# sb-sonata-industriaal.net
KiCad netlist of a schematic drawn in Altium Designer
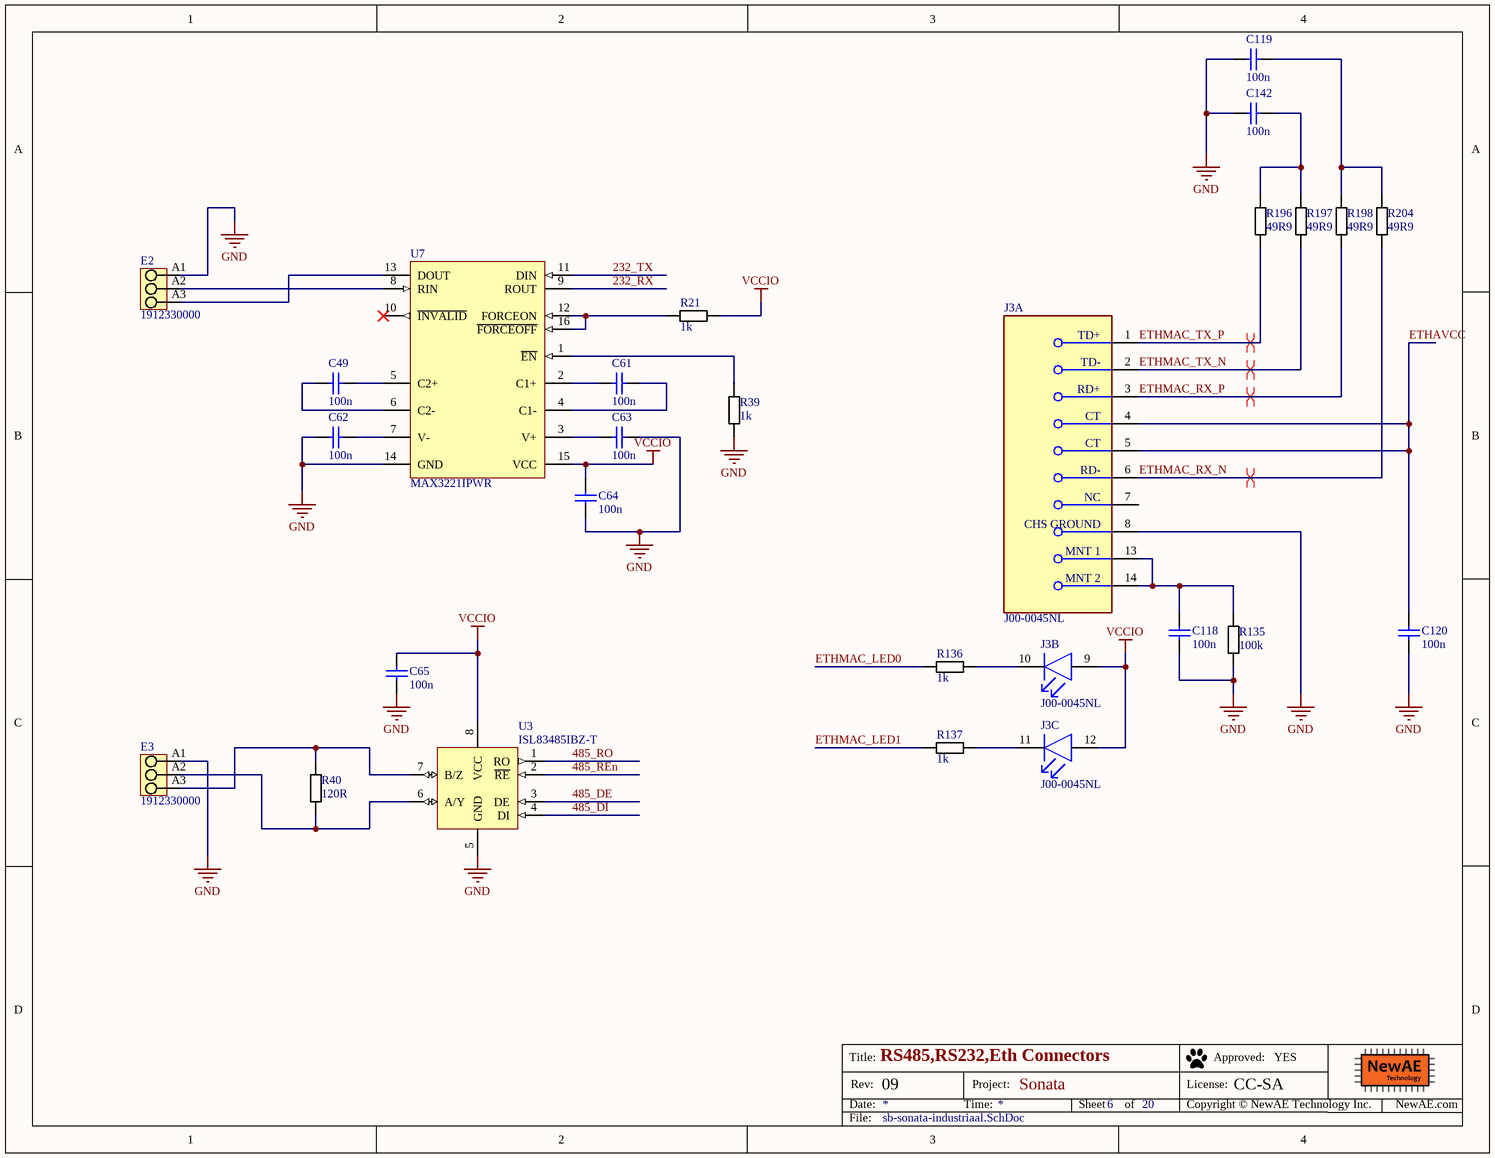
[diagram p0: sb-sonata-industriaal.SchDoc]

(export (version "E")
  (design (tool "Eeschema 10.0.6"))
  (components
    (comp (ref "C49")
      (value "100n")
      (footprint "CAPC0402_M")
      (description "100n, 0402")
      (fields (field (name "PART NUMBER") "CCHIP-100n-0402"))
      (libsource (lib "NewAE_AltiumLib") (part "CAP"))
    )
    (comp (ref "C61")
      (value "100n")
      (footprint "CAPC0402_M")
      (description "100n, 0402")
      (fields (field (name "PART NUMBER") "CCHIP-100n-0402"))
      (libsource (lib "NewAE_AltiumLib") (part "CAP"))
    )
    (comp (ref "C62")
      (value "100n")
      (footprint "CAPC0402_M")
      (description "100n, 0402")
      (fields (field (name "PART NUMBER") "CCHIP-100n-0402"))
      (libsource (lib "NewAE_AltiumLib") (part "CAP"))
    )
    (comp (ref "C63")
      (value "100n")
      (footprint "CAPC0402_M")
      (description "100n, 0402")
      (fields (field (name "PART NUMBER") "CCHIP-100n-0402"))
      (libsource (lib "NewAE_AltiumLib") (part "CAP"))
    )
    (comp (ref "C64")
      (value "100n")
      (footprint "CAPC0402_M")
      (description "100n, 0402")
      (fields (field (name "PART NUMBER") "CCHIP-100n-0402"))
      (libsource (lib "NewAE_AltiumLib") (part "CAP"))
    )
    (comp (ref "C65")
      (value "100n")
      (footprint "CAPC0402_M")
      (description "100n, 0402")
      (fields (field (name "PART NUMBER") "CCHIP-100n-0402"))
      (libsource (lib "NewAE_AltiumLib") (part "CAP"))
    )
    (comp (ref "C118")
      (value "100n")
      (footprint "CAPC0402_M")
      (description "100n, 0402")
      (fields (field (name "PART NUMBER") "CCHIP-100n-0402"))
      (libsource (lib "NewAE_AltiumLib") (part "CAP"))
    )
    (comp (ref "C119")
      (value "100n")
      (footprint "CAPC0402_M")
      (description "100n, 0402")
      (fields (field (name "PART NUMBER") "CCHIP-100n-0402"))
      (libsource (lib "NewAE_AltiumLib") (part "CAP"))
    )
    (comp (ref "C120")
      (value "100n")
      (footprint "CAPC0402_M")
      (description "100n, 0402")
      (fields (field (name "PART NUMBER") "CCHIP-100n-0402"))
      (libsource (lib "NewAE_AltiumLib") (part "CAP"))
    )
    (comp (ref "C142")
      (value "100n")
      (footprint "CAPC0402_M")
      (description "100n, 0402")
      (fields (field (name "PART NUMBER") "CCHIP-100n-0402"))
      (libsource (lib "NewAE_AltiumLib") (part "CAP"))
    )
    (comp (ref "E2")
      (value "1912330000")
      (footprint "PS_3_5_90_03")
      (description "OMNIMATE Signal - series PS")
      (fields (field (name "MANUFACTURER") "Weidmueller"))
      (libsource (lib "Altium Content Vault") (part "Terminal_03_1x03"))
    )
    (comp (ref "E3")
      (value "1912330000")
      (footprint "PS_3_5_90_03")
      (description "OMNIMATE Signal - series PS")
      (fields (field (name "MANUFACTURER") "Weidmueller"))
      (libsource (lib "Altium Content Vault") (part "Terminal_03_1x03"))
    )
    (comp (ref "J3")
      (value "J00-0045NL")
      (footprint "FP-J00-0045NL-MFG")
      (description "CONN JACK 1PORT 100 BASE-TX PCB")
      (libsource (lib "") (part "9e414223d7443300137682b695b44b7_1"))
    )
    (comp (ref "R21")
      (value "1k")
      (footprint "RESC1608X55N")
      (description "1k res, 0603, 1%, 1/10W")
      (fields (field (name "PART NUMBER") "RCHIP-1K-0603") (field (name "TOLERANCE") "1%"))
      (libsource (lib "") (part "RES-EU_1"))
    )
    (comp (ref "R39")
      (value "1k")
      (footprint "RESC1608X55N")
      (description "1k res, 0603, 1%, 1/10W")
      (fields (field (name "PART NUMBER") "RCHIP-1K-0603") (field (name "TOLERANCE") "1%"))
      (libsource (lib "") (part "RES-EU_2"))
    )
    (comp (ref "R40")
      (value "120R")
      (footprint "RESC1608X55N")
      (description "120R res, 0603, 1%, 1/10W")
      (fields (field (name "PART NUMBER") "RCHIP-120R-0603") (field (name "TOLERANCE") "1%"))
      (libsource (lib "NewAE_AltiumLib") (part "RES-EU"))
    )
    (comp (ref "R135")
      (value "100k")
      (footprint "RESC1005X40N")
      (description "100k res, 0402, 1%, 1/16W")
      (fields (field (name "PART NUMBER") "RCHIP-100K-0402") (field (name "TOLERANCE") "1%"))
      (libsource (lib "NewAE_AltiumLib") (part "RES-EU"))
    )
    (comp (ref "R136")
      (value "1k")
      (footprint "RESC1608X55N")
      (description "1k res, 0603, 1%, 1/10W")
      (fields (field (name "PART NUMBER") "RCHIP-1K-0603") (field (name "TOLERANCE") "1%"))
      (libsource (lib "") (part "RES-EU_1"))
    )
    (comp (ref "R137")
      (value "1k")
      (footprint "RESC1608X55N")
      (description "1k res, 0603, 1%, 1/10W")
      (fields (field (name "PART NUMBER") "RCHIP-1K-0603") (field (name "TOLERANCE") "1%"))
      (libsource (lib "") (part "RES-EU_1"))
    )
    (comp (ref "R196")
      (value "49R9")
      (footprint "RESC2012X70N")
      (description "49r9 res, 0805, 1%, 1/8W")
      (fields (field (name "PART NUMBER") "RCHIP-49R9-0805") (field (name "TOLERANCE") "1%"))
      (libsource (lib "NewAE_AltiumLib") (part "RES-EU"))
    )
    (comp (ref "R197")
      (value "49R9")
      (footprint "RESC2012X70N")
      (description "49r9 res, 0805, 1%, 1/8W")
      (fields (field (name "PART NUMBER") "RCHIP-49R9-0805") (field (name "TOLERANCE") "1%"))
      (libsource (lib "NewAE_AltiumLib") (part "RES-EU"))
    )
    (comp (ref "R198")
      (value "49R9")
      (footprint "RESC2012X70N")
      (description "49r9 res, 0805, 1%, 1/8W")
      (fields (field (name "PART NUMBER") "RCHIP-49R9-0805") (field (name "TOLERANCE") "1%"))
      (libsource (lib "NewAE_AltiumLib") (part "RES-EU"))
    )
    (comp (ref "R204")
      (value "49R9")
      (footprint "RESC2012X70N")
      (description "49r9 res, 0805, 1%, 1/8W")
      (fields (field (name "PART NUMBER") "RCHIP-49R9-0805") (field (name "TOLERANCE") "1%"))
      (libsource (lib "NewAE_AltiumLib") (part "RES-EU"))
    )
    (comp (ref "U3")
      (value "ISL83485IBZ-T")
      (footprint "SOIC8_NARROW")
      (description "IC TXRX RS422/RS485")
      (fields (field (name "PART NUMBER") "ISL83485I"))
      (libsource (lib "NewAE_AltiumLib") (part "ISL32458E"))
    )
    (comp (ref "U7")
      (value "MAX3221IPWR")
      (footprint "PW0016A_L")
      (libsource (lib "Altium Content Vault") (part "TI-MAX3221-TSSOP_PW-16"))
    )
  )
  (nets
    (net (code "1") (name "/232_RX") (class "Default")
      (node (ref "U7") (pin "9") (pinfunction "ROUT_9") (pintype "tri_state"))
    )
    (net (code "2") (name "/232_TX") (class "Default")
      (node (ref "U7") (pin "11") (pinfunction "DIN_11") (pintype "input"))
    )
    (net (code "3") (name "/485_DE") (class "Default")
      (node (ref "U3") (pin "3") (pinfunction "DE_3") (pintype "input"))
    )
    (net (code "4") (name "/485_DI") (class "Default")
      (node (ref "U3") (pin "4") (pinfunction "DI_4") (pintype "input"))
    )
    (net (code "5") (name "/485_REn") (class "Default")
      (node (ref "U3") (pin "2") (pinfunction "~{RE}_2") (pintype "input"))
    )
    (net (code "6") (name "/485_RO") (class "Default")
      (node (ref "U3") (pin "1") (pinfunction "RO_1") (pintype "output"))
    )
    (net (code "7") (name "/ETHAVCC") (class "Default")
      (node (ref "C120") (pin "1") (pinfunction "1_1") (pintype "passive"))
      (node (ref "J3") (pin "4") (pinfunction "CT_4") (pintype "passive"))
      (node (ref "J3") (pin "5") (pinfunction "CT_5") (pintype "passive"))
    )
    (net (code "8") (name "/ETHMAC_LED0") (class "Default")
      (node (ref "R136") (pin "1") (pinfunction "1_1") (pintype "passive"))
    )
    (net (code "9") (name "/ETHMAC_LED1") (class "Default")
      (node (ref "R137") (pin "1") (pinfunction "1_1") (pintype "passive"))
    )
    (net (code "10") (name "/ETHMAC_RX_N") (class "Default")
      (node (ref "J3") (pin "6") (pinfunction "RD-_6") (pintype "passive"))
      (node (ref "R204") (pin "2") (pinfunction "2_2") (pintype "passive"))
    )
    (net (code "11") (name "/ETHMAC_RX_P") (class "Default")
      (node (ref "J3") (pin "3") (pinfunction "RD+_3") (pintype "passive"))
      (node (ref "R198") (pin "2") (pinfunction "2_2") (pintype "passive"))
    )
    (net (code "12") (name "/ETHMAC_TX_N") (class "Default")
      (node (ref "J3") (pin "2") (pinfunction "TD-_2") (pintype "passive"))
      (node (ref "R197") (pin "2") (pinfunction "2_2") (pintype "passive"))
    )
    (net (code "13") (name "/ETHMAC_TX_P") (class "Default")
      (node (ref "J3") (pin "1") (pinfunction "TD+_1") (pintype "passive"))
      (node (ref "R196") (pin "2") (pinfunction "2_2") (pintype "passive"))
    )
    (net (code "14") (name "GND") (class "Default")
      (node (ref "C118") (pin "2") (pinfunction "2_2") (pintype "passive"))
      (node (ref "C119") (pin "1") (pinfunction "1_1") (pintype "passive"))
      (node (ref "C120") (pin "2") (pinfunction "2_2") (pintype "passive"))
      (node (ref "C142") (pin "1") (pinfunction "1_1") (pintype "passive"))
      (node (ref "C62") (pin "2") (pinfunction "2_2") (pintype "passive"))
      (node (ref "C63") (pin "1") (pinfunction "1_1") (pintype "passive"))
      (node (ref "C64") (pin "1") (pinfunction "1_1") (pintype "passive"))
      (node (ref "C65") (pin "2") (pinfunction "2_2") (pintype "passive"))
      (node (ref "E2") (pin "A1") (pinfunction "A1_A1") (pintype "passive"))
      (node (ref "E3") (pin "A1") (pinfunction "A1_A1") (pintype "passive"))
      (node (ref "J3") (pin "8") (pinfunction "CHS_GROUND_8") (pintype "passive"))
      (node (ref "R135") (pin "2") (pinfunction "2_2") (pintype "passive"))
      (node (ref "R39") (pin "2") (pinfunction "2_2") (pintype "passive"))
      (node (ref "U3") (pin "5") (pinfunction "GND_5") (pintype "power_in"))
      (node (ref "U7") (pin "14") (pinfunction "GND_14") (pintype "power_in"))
    )
    (net (code "15") (name "Net-(C119-Pad2)") (class "Default")
      (node (ref "C119") (pin "2") (pinfunction "2_2") (pintype "passive"))
      (node (ref "R198") (pin "1") (pinfunction "1_1") (pintype "passive"))
      (node (ref "R204") (pin "1") (pinfunction "1_1") (pintype "passive"))
    )
    (net (code "16") (name "Net-(C142-Pad2)") (class "Default")
      (node (ref "C142") (pin "2") (pinfunction "2_2") (pintype "passive"))
      (node (ref "R196") (pin "1") (pinfunction "1_1") (pintype "passive"))
      (node (ref "R197") (pin "1") (pinfunction "1_1") (pintype "passive"))
    )
    (net (code "17") (name "Net-(J3A-MNT_1)") (class "Default")
      (node (ref "C118") (pin "1") (pinfunction "1_1") (pintype "passive"))
      (node (ref "J3") (pin "13") (pinfunction "MNT_1_13") (pintype "passive"))
      (node (ref "J3") (pin "14") (pinfunction "MNT_2_14") (pintype "passive"))
      (node (ref "R135") (pin "1") (pinfunction "1_1") (pintype "passive"))
    )
    (net (code "18") (name "Net-(J3B-GREEN_C)") (class "Default")
      (node (ref "J3") (pin "10") (pinfunction "GREEN_C_10") (pintype "passive"))
      (node (ref "R136") (pin "2") (pinfunction "2_2") (pintype "passive"))
    )
    (net (code "19") (name "Net-(J3C-YELLOW_CATHODE)") (class "Default")
      (node (ref "J3") (pin "11") (pinfunction "YELLOW_CATHODE_11") (pintype "passive"))
      (node (ref "R137") (pin "2") (pinfunction "2_2") (pintype "passive"))
    )
    (net (code "20") (name "Net-(U3-A{slash}Y)") (class "Default")
      (node (ref "E3") (pin "A2") (pinfunction "A2_A2") (pintype "passive"))
      (node (ref "R40") (pin "2") (pinfunction "2_2") (pintype "passive"))
      (node (ref "U3") (pin "6") (pinfunction "A/Y_6") (pintype "bidirectional"))
    )
    (net (code "21") (name "Net-(U3-B{slash}Z)") (class "Default")
      (node (ref "E3") (pin "A3") (pinfunction "A3_A3") (pintype "passive"))
      (node (ref "R40") (pin "1") (pinfunction "1_1") (pintype "passive"))
      (node (ref "U3") (pin "7") (pinfunction "B/Z_7") (pintype "bidirectional"))
    )
    (net (code "22") (name "Net-(U7-C1+)") (class "Default")
      (node (ref "C61") (pin "2") (pinfunction "2_2") (pintype "passive"))
      (node (ref "U7") (pin "2") (pinfunction "C1+_2") (pintype "passive"))
    )
    (net (code "23") (name "Net-(U7-C1-)") (class "Default")
      (node (ref "C61") (pin "1") (pinfunction "1_1") (pintype "passive"))
      (node (ref "U7") (pin "4") (pinfunction "C1-_4") (pintype "passive"))
    )
    (net (code "24") (name "Net-(U7-C2+)") (class "Default")
      (node (ref "C49") (pin "1") (pinfunction "1_1") (pintype "passive"))
      (node (ref "U7") (pin "5") (pinfunction "C2+_5") (pintype "passive"))
    )
    (net (code "25") (name "Net-(U7-C2-)") (class "Default")
      (node (ref "C49") (pin "2") (pinfunction "2_2") (pintype "passive"))
      (node (ref "U7") (pin "6") (pinfunction "C2-_6") (pintype "passive"))
    )
    (net (code "26") (name "Net-(U7-DOUT)") (class "Default")
      (node (ref "E2") (pin "A3") (pinfunction "A3_A3") (pintype "passive"))
      (node (ref "U7") (pin "13") (pinfunction "DOUT_13") (pintype "tri_state"))
    )
    (net (code "27") (name "Net-(U7-FORCEON)") (class "Default")
      (node (ref "R21") (pin "1") (pinfunction "1_1") (pintype "passive"))
      (node (ref "U7") (pin "12") (pinfunction "FORCEON_12") (pintype "input"))
      (node (ref "U7") (pin "16") (pinfunction "~{FORCEOFF}_16") (pintype "input"))
    )
    (net (code "28") (name "Net-(U7-RIN)") (class "Default")
      (node (ref "E2") (pin "A2") (pinfunction "A2_A2") (pintype "passive"))
      (node (ref "U7") (pin "8") (pinfunction "RIN_8") (pintype "input"))
    )
    (net (code "29") (name "Net-(U7-V+)") (class "Default")
      (node (ref "C63") (pin "2") (pinfunction "2_2") (pintype "passive"))
      (node (ref "U7") (pin "3") (pinfunction "V+_3") (pintype "power_in"))
    )
    (net (code "30") (name "Net-(U7-V-)") (class "Default")
      (node (ref "C62") (pin "1") (pinfunction "1_1") (pintype "passive"))
      (node (ref "U7") (pin "7") (pinfunction "V-_7") (pintype "power_in"))
    )
    (net (code "31") (name "Net-(U7-~{EN})") (class "Default")
      (node (ref "R39") (pin "1") (pinfunction "1_1") (pintype "passive"))
      (node (ref "U7") (pin "1") (pinfunction "~{EN}_1") (pintype "input"))
    )
    (net (code "32") (name "VCCIO") (class "Default")
      (node (ref "C64") (pin "2") (pinfunction "2_2") (pintype "passive"))
      (node (ref "C65") (pin "1") (pinfunction "1_1") (pintype "passive"))
      (node (ref "J3") (pin "12") (pinfunction "YELLOW_ANODE_12") (pintype "passive"))
      (node (ref "J3") (pin "9") (pinfunction "GREEN_A_9") (pintype "passive"))
      (node (ref "R21") (pin "2") (pinfunction "2_2") (pintype "passive"))
      (node (ref "U3") (pin "8") (pinfunction "VCC_8") (pintype "power_in"))
      (node (ref "U7") (pin "15") (pinfunction "VCC_15") (pintype "power_in"))
    )
    (net (code "33") (name "unconnected-(J3A-NC-Pad7)") (class "Default")
      (node (ref "J3") (pin "7") (pinfunction "NC_7") (pintype "passive"))
    )
    (net (code "34") (name "unconnected-(U7-~{INVALID}-Pad10)") (class "Default")
      (node (ref "U7") (pin "10") (pinfunction "~{INVALID}_10") (pintype "output+no_connect"))
    )
  )
)
